# LTM8032_5V5.net
KiCad netlist of a schematic drawn in Altium Designer
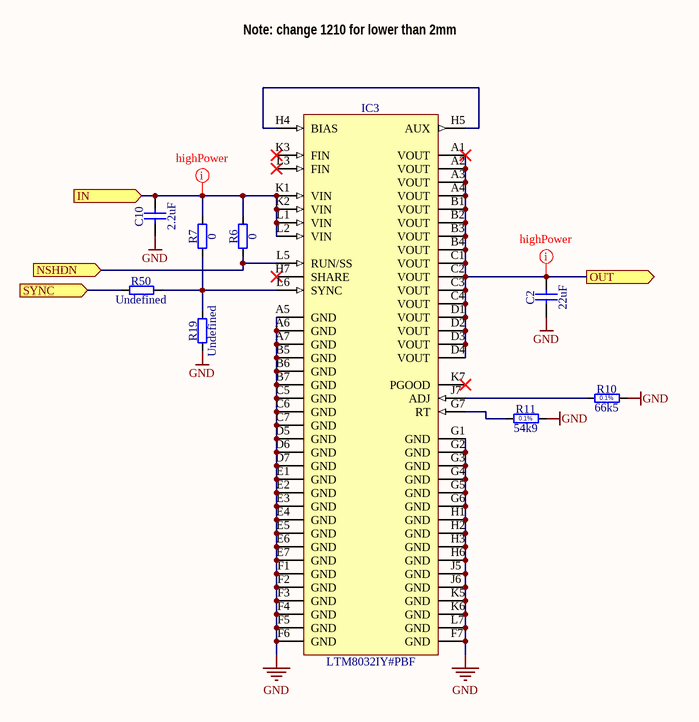
[diagram p0: LTM8032_5V5.SchDoc]

(export (version "E")
  (design (tool "Eeschema 10.0.6"))
  (components
    (comp (ref "C2")
      (value "22uF")
      (footprint "CAPC3216X180N")
      (description "Non-polarised capacitor")
      (fields
        (field (name "PART NUMBER") "CC1206_22UF_10V_10%_X7R")
        (field (name "VOLTAGE") "10V")
        (field (name "AUTHOR") "CERN DEM JLC")
      )
      (libsource (lib "Capacitors") (part "Capacitor - non polarized"))
    )
    (comp (ref "C10")
      (value "2.2uF")
      (footprint "CAPC2012X140N")
      (description "Non-polarised capacitor")
      (fields
        (field (name "PART NUMBER") "CC0805_2.2UF_50V_10%_X7R")
        (field (name "VOLTAGE") "50V")
        (field (name "AUTHOR") "CERN DEM JLC")
      )
      (libsource (lib "Capacitors") (part "Capacitor - non polarized"))
    )
    (comp (ref "IC3")
      (value "LTM8032IY#PBF")
      (footprint "BGA71C127P7X11_900X1500X362")
      (description "3V-36V To 0.8V-10V, Iout 2A Ultralow Noise EMC Compliant DC/DC uModule")
      (fields (field (name "MANUFACTURER") "LINEAR TECHNOLOGY") (field (name "AUTHOR") "CERN DEM BC"))
      (libsource (lib "ICs And Semiconductors") (part "LTM8032"))
    )
    (comp (ref "R6")
      (value "0")
      (footprint "RESC1608X55N")
      (description "Resistor")
      (fields
        (field (name "PART NUMBER") "R0603_0R_JUMPER")
        (field (name "MANUFACTURER") "GENERIC")
        (field (name "AUTHOR") "CERN DEM JLC")
      )
      (libsource (lib "Resistors") (part "Resistor"))
    )
    (comp (ref "R7")
      (value "0")
      (footprint "RESC1608X55N")
      (description "Resistor")
      (fields
        (field (name "PART NUMBER") "R0603_0R_JUMPER")
        (field (name "MANUFACTURER") "GENERIC")
        (field (name "AUTHOR") "CERN DEM JLC")
      )
      (libsource (lib "Resistors") (part "Resistor"))
    )
    (comp (ref "R10")
      (value "66k5")
      (footprint "RESC1608X55N")
      (description "Resistor - 0.1%")
      (fields
        (field (name "PART NUMBER") "R0603_66K5_0.1%_0.063W_10PPM")
        (field (name "POWER") "0.063W")
        (field (name "AUTHOR") "CERN DEM JLC")
      )
      (libsource (lib "Resistors") (part "Resistor - 0.1%"))
    )
    (comp (ref "R11")
      (value "54k9")
      (footprint "RESC1608X55N")
      (description "Resistor - 0.1%")
      (fields
        (field (name "PART NUMBER") "R0603_54K9_0.1%_0.063W_10PPM")
        (field (name "POWER") "0.063W")
        (field (name "AUTHOR") "CERN DEM JLC")
      )
      (libsource (lib "Resistors") (part "Resistor - 0.1%"))
    )
    (comp (ref "R19")
      (value "Undefined")
      (footprint "RESC1608X55N")
      (description "Resistor")
      (fields (field (name "PART NUMBER") "R0603_NO-VALUE") (field (name "AUTHOR") "CERN DEM JLC"))
      (libsource (lib "Resistors") (part "Resistor"))
    )
    (comp (ref "R50")
      (value "Undefined")
      (footprint "RESC1608X55N")
      (description "Resistor")
      (fields (field (name "PART NUMBER") "R0603_NO-VALUE") (field (name "AUTHOR") "CERN DEM JLC"))
      (libsource (lib "Resistors") (part "Resistor"))
    )
  )
  (nets
    (net (code "1") (name "/IN") (class "Default")
      (node (ref "C10") (pin "2") (pinfunction "2_2") (pintype "passive"))
      (node (ref "IC3") (pin "K1") (pinfunction "VIN_K1") (pintype "input"))
      (node (ref "IC3") (pin "K2") (pinfunction "VIN_K2") (pintype "input"))
      (node (ref "IC3") (pin "L1") (pinfunction "VIN_L1") (pintype "input"))
      (node (ref "IC3") (pin "L2") (pinfunction "VIN_L2") (pintype "input"))
      (node (ref "R6") (pin "2") (pinfunction "2_2") (pintype "passive"))
      (node (ref "R7") (pin "2") (pinfunction "2_2") (pintype "passive"))
    )
    (net (code "2") (name "/NSHDN") (class "Default")
      (node (ref "IC3") (pin "L5") (pinfunction "RUN/SS_L5") (pintype "input"))
      (node (ref "R6") (pin "1") (pinfunction "1_1") (pintype "passive"))
    )
    (net (code "3") (name "/OUT") (class "Default")
      (node (ref "C2") (pin "2") (pinfunction "2_2") (pintype "passive"))
      (node (ref "IC3") (pin "A1") (pinfunction "VOUT_A1") (pintype "power_in"))
      (node (ref "IC3") (pin "A2") (pinfunction "VOUT_A2") (pintype "power_in"))
      (node (ref "IC3") (pin "A3") (pinfunction "VOUT_A3") (pintype "power_in"))
      (node (ref "IC3") (pin "A4") (pinfunction "VOUT_A4") (pintype "power_in"))
      (node (ref "IC3") (pin "B1") (pinfunction "VOUT_B1") (pintype "power_in"))
      (node (ref "IC3") (pin "B2") (pinfunction "VOUT_B2") (pintype "power_in"))
      (node (ref "IC3") (pin "B3") (pinfunction "VOUT_B3") (pintype "power_in"))
      (node (ref "IC3") (pin "B4") (pinfunction "VOUT_B4") (pintype "power_in"))
      (node (ref "IC3") (pin "C1") (pinfunction "VOUT_C1") (pintype "power_in"))
      (node (ref "IC3") (pin "C2") (pinfunction "VOUT_C2") (pintype "power_in"))
      (node (ref "IC3") (pin "C3") (pinfunction "VOUT_C3") (pintype "power_in"))
      (node (ref "IC3") (pin "C4") (pinfunction "VOUT_C4") (pintype "power_in"))
      (node (ref "IC3") (pin "D1") (pinfunction "VOUT_D1") (pintype "power_in"))
      (node (ref "IC3") (pin "D2") (pinfunction "VOUT_D2") (pintype "power_in"))
      (node (ref "IC3") (pin "D3") (pinfunction "VOUT_D3") (pintype "power_in"))
      (node (ref "IC3") (pin "D4") (pinfunction "VOUT_D4") (pintype "power_in"))
    )
    (net (code "4") (name "/SYNC") (class "Default")
      (node (ref "R50") (pin "1") (pinfunction "1_1") (pintype "passive"))
    )
    (net (code "5") (name "GND") (class "Default")
      (node (ref "C10") (pin "1") (pinfunction "1_1") (pintype "passive"))
      (node (ref "C2") (pin "1") (pinfunction "1_1") (pintype "passive"))
      (node (ref "IC3") (pin "A5") (pinfunction "GND_A5") (pintype "power_in"))
      (node (ref "IC3") (pin "A6") (pinfunction "GND_A6") (pintype "power_in"))
      (node (ref "IC3") (pin "A7") (pinfunction "GND_A7") (pintype "power_in"))
      (node (ref "IC3") (pin "B5") (pinfunction "GND_B5") (pintype "power_in"))
      (node (ref "IC3") (pin "B6") (pinfunction "GND_B6") (pintype "power_in"))
      (node (ref "IC3") (pin "B7") (pinfunction "GND_B7") (pintype "power_in"))
      (node (ref "IC3") (pin "C5") (pinfunction "GND_C5") (pintype "power_in"))
      (node (ref "IC3") (pin "C6") (pinfunction "GND_C6") (pintype "power_in"))
      (node (ref "IC3") (pin "C7") (pinfunction "GND_C7") (pintype "power_in"))
      (node (ref "IC3") (pin "D5") (pinfunction "GND_D5") (pintype "power_in"))
      (node (ref "IC3") (pin "D6") (pinfunction "GND_D6") (pintype "power_in"))
      (node (ref "IC3") (pin "D7") (pinfunction "GND_D7") (pintype "power_in"))
      (node (ref "IC3") (pin "E1") (pinfunction "GND_E1") (pintype "power_in"))
      (node (ref "IC3") (pin "E2") (pinfunction "GND_E2") (pintype "power_in"))
      (node (ref "IC3") (pin "E3") (pinfunction "GND_E3") (pintype "power_in"))
      (node (ref "IC3") (pin "E4") (pinfunction "GND_E4") (pintype "power_in"))
      (node (ref "IC3") (pin "E5") (pinfunction "GND_E5") (pintype "power_in"))
      (node (ref "IC3") (pin "E6") (pinfunction "GND_E6") (pintype "power_in"))
      (node (ref "IC3") (pin "E7") (pinfunction "GND_E7") (pintype "power_in"))
      (node (ref "IC3") (pin "F1") (pinfunction "GND_F1") (pintype "power_in"))
      (node (ref "IC3") (pin "F2") (pinfunction "GND_F2") (pintype "power_in"))
      (node (ref "IC3") (pin "F3") (pinfunction "GND_F3") (pintype "power_in"))
      (node (ref "IC3") (pin "F4") (pinfunction "GND_F4") (pintype "power_in"))
      (node (ref "IC3") (pin "F5") (pinfunction "GND_F5") (pintype "power_in"))
      (node (ref "IC3") (pin "F6") (pinfunction "GND_F6") (pintype "power_in"))
      (node (ref "IC3") (pin "F7") (pinfunction "GND_F7") (pintype "power_in"))
      (node (ref "IC3") (pin "G1") (pinfunction "GND_G1") (pintype "power_in"))
      (node (ref "IC3") (pin "G2") (pinfunction "GND_G2") (pintype "power_in"))
      (node (ref "IC3") (pin "G3") (pinfunction "GND_G3") (pintype "power_in"))
      (node (ref "IC3") (pin "G4") (pinfunction "GND_G4") (pintype "power_in"))
      (node (ref "IC3") (pin "G5") (pinfunction "GND_G5") (pintype "power_in"))
      (node (ref "IC3") (pin "G6") (pinfunction "GND_G6") (pintype "power_in"))
      (node (ref "IC3") (pin "H1") (pinfunction "GND_H1") (pintype "power_in"))
      (node (ref "IC3") (pin "H2") (pinfunction "GND_H2") (pintype "power_in"))
      (node (ref "IC3") (pin "H3") (pinfunction "GND_H3") (pintype "power_in"))
      (node (ref "IC3") (pin "H6") (pinfunction "GND_H6") (pintype "power_in"))
      (node (ref "IC3") (pin "J5") (pinfunction "GND_J5") (pintype "power_in"))
      (node (ref "IC3") (pin "J6") (pinfunction "GND_J6") (pintype "power_in"))
      (node (ref "IC3") (pin "K5") (pinfunction "GND_K5") (pintype "power_in"))
      (node (ref "IC3") (pin "K6") (pinfunction "GND_K6") (pintype "power_in"))
      (node (ref "IC3") (pin "L7") (pinfunction "GND_L7") (pintype "power_in"))
      (node (ref "R10") (pin "2") (pinfunction "2_2") (pintype "passive"))
      (node (ref "R11") (pin "2") (pinfunction "2_2") (pintype "passive"))
      (node (ref "R19") (pin "1") (pinfunction "1_1") (pintype "passive"))
    )
    (net (code "6") (name "Net-(IC3-ADJ)") (class "Default")
      (node (ref "IC3") (pin "J7") (pinfunction "ADJ_J7") (pintype "input"))
      (node (ref "R10") (pin "1") (pinfunction "1_1") (pintype "passive"))
    )
    (net (code "7") (name "Net-(IC3-AUX)") (class "Default")
      (node (ref "IC3") (pin "H4") (pinfunction "BIAS_H4") (pintype "input"))
      (node (ref "IC3") (pin "H5") (pinfunction "AUX_H5") (pintype "output"))
    )
    (net (code "8") (name "Net-(IC3-RT)") (class "Default")
      (node (ref "IC3") (pin "G7") (pinfunction "RT_G7") (pintype "input"))
      (node (ref "R11") (pin "1") (pinfunction "1_1") (pintype "passive"))
    )
    (net (code "9") (name "Net-(IC3-SYNC)") (class "Default")
      (node (ref "IC3") (pin "L6") (pinfunction "SYNC_L6") (pintype "input"))
      (node (ref "R19") (pin "2") (pinfunction "2_2") (pintype "passive"))
      (node (ref "R50") (pin "2") (pinfunction "2_2") (pintype "passive"))
      (node (ref "R7") (pin "1") (pinfunction "1_1") (pintype "passive"))
    )
    (net (code "10") (name "unconnected-(IC3-FIN-PadK3)") (class "Default")
      (node (ref "IC3") (pin "K3") (pinfunction "FIN_K3") (pintype "input+no_connect"))
    )
    (net (code "11") (name "unconnected-(IC3-FIN-PadL3)") (class "Default")
      (node (ref "IC3") (pin "L3") (pinfunction "FIN_L3") (pintype "input+no_connect"))
    )
    (net (code "12") (name "unconnected-(IC3-PGOOD-PadK7)") (class "Default")
      (node (ref "IC3") (pin "K7") (pinfunction "PGOOD_K7") (pintype "open_collector+no_connect"))
    )
    (net (code "13") (name "unconnected-(IC3-SHARE-PadH7)") (class "Default")
      (node (ref "IC3") (pin "H7") (pinfunction "SHARE_H7") (pintype "passive+no_connect"))
    )
  )
)
